# i3_Botao.net
KiCad netlist of a schematic drawn in EAGLE
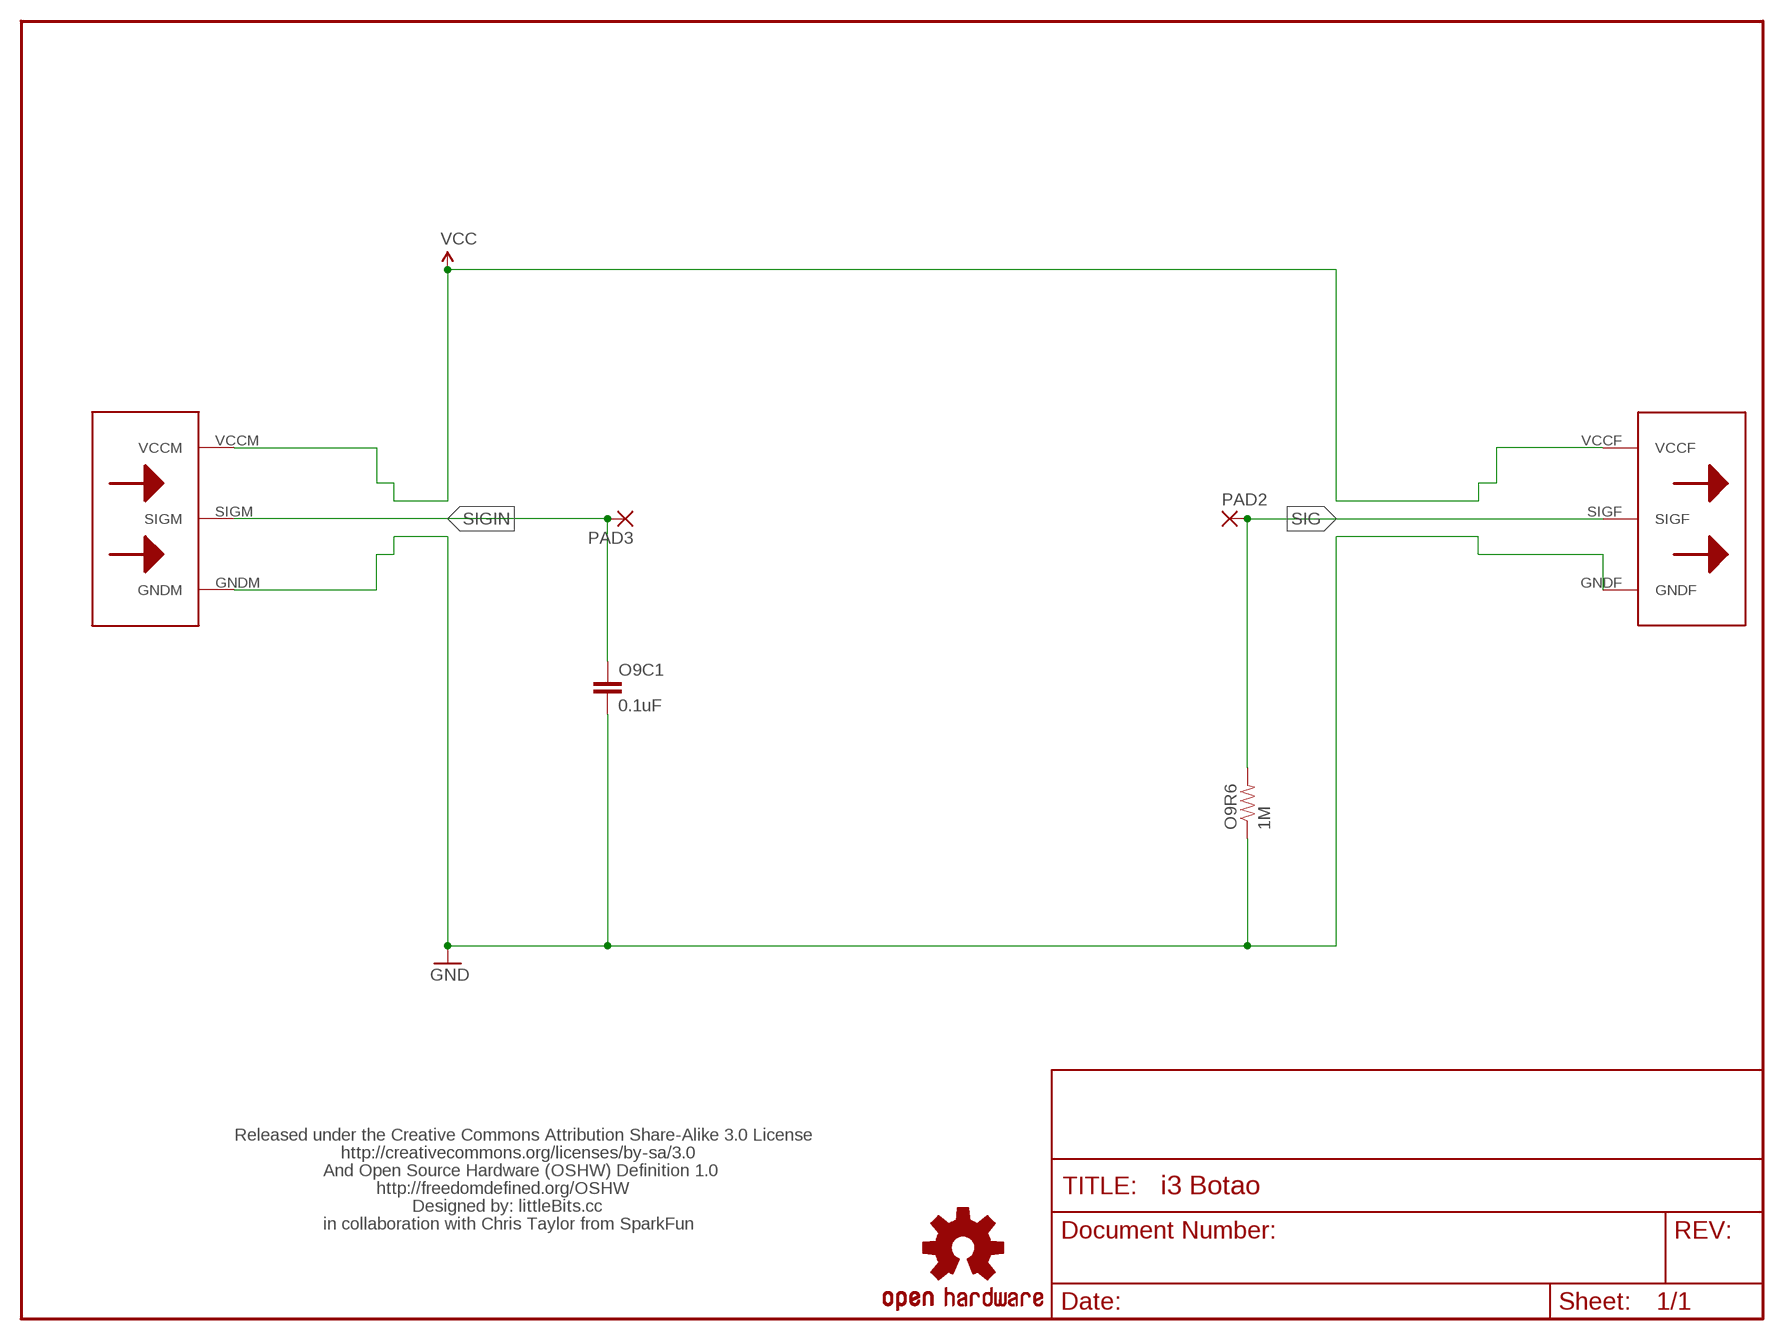
[diagram p0: schematic, sheet 1]

(export (version "E")
  (design (tool "Eeschema 10.0.6"))
  (components
    (comp (ref "O9C1")
      (value "0.1uF")
      (footprint "eagle-import:1206")
      (libsource (lib "eagle-import") (part "CAP1206"))
    )
    (comp (ref "O9R6")
      (value "1M")
      (footprint "eagle-import:0805")
      (libsource (lib "eagle-import") (part "RESISTOR"))
    )
    (comp (ref "PAD2")
      (value "SMD5")
      (footprint "eagle-import:SMD2,54-5,08")
      (libsource (lib "eagle-import") (part "SMD5"))
    )
    (comp (ref "PAD3")
      (value "SMD5")
      (footprint "eagle-import:SMD2,54-5,08")
      (libsource (lib "eagle-import") (part "SMD5"))
    )
    (comp (ref "U$1")
      (value "LB_CREDITS")
      (footprint "eagle-import:OSHWCREDIT")
      (libsource (lib "eagle-import") (part "LB_CREDITS"))
    )
    (comp (ref "U$2")
      (value "BIGBIT")
      (footprint "eagle-import:BIGBIT")
      (libsource (lib "eagle-import") (part "BIGBIT"))
    )
    (comp (ref "U$3")
      (value "OSHW-LOGOL")
      (footprint "eagle-import:OSHW-LOGO-L")
      (libsource (lib "eagle-import") (part "OSHW-LOGOL"))
    )
  )
  (nets
    (net (code "1") (name "GND") (class "Default")
      (node (ref "O9C1") (pin "2") (pinfunction "2_2") (pintype "passive"))
      (node (ref "O9R6") (pin "1") (pinfunction "1_1") (pintype "passive"))
      (node (ref "U$2") (pin "GNDF") (pinfunction "GNDF_GNDF") (pintype "bidirectional"))
      (node (ref "U$2") (pin "GNDM") (pinfunction "GNDM_GNDM") (pintype "bidirectional"))
    )
    (net (code "2") (name "SIG") (class "Default")
      (node (ref "O9R6") (pin "2") (pinfunction "2_2") (pintype "passive"))
      (node (ref "PAD2") (pin "1") (pinfunction "P_1") (pintype "passive"))
      (node (ref "U$2") (pin "SIGF") (pinfunction "SIGF_SIGF") (pintype "bidirectional"))
    )
    (net (code "3") (name "SIGIN") (class "Default")
      (node (ref "O9C1") (pin "1") (pinfunction "1_1") (pintype "passive"))
      (node (ref "PAD3") (pin "1") (pinfunction "P_1") (pintype "passive"))
      (node (ref "U$2") (pin "SIGM") (pinfunction "SIGM_SIGM") (pintype "bidirectional"))
    )
    (net (code "4") (name "VCC") (class "Default")
      (node (ref "U$2") (pin "VCCF") (pinfunction "VCCF_VCCF") (pintype "bidirectional"))
      (node (ref "U$2") (pin "VCCM") (pinfunction "VCCM_VCCM") (pintype "bidirectional"))
    )
  )
)
